# ldo_sch.net
KiCad netlist of a schematic drawn in Altium Designer
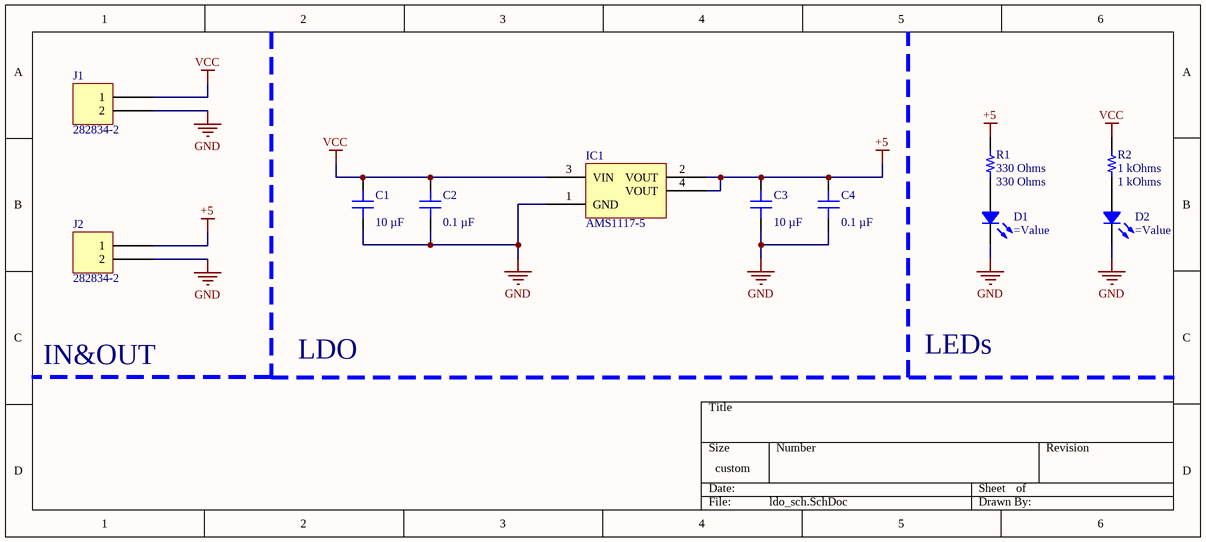
[diagram p0: ldo_sch.SchDoc]

(export (version "E")
  (design (tool "Eeschema 10.0.6"))
  (components
    (comp (ref "C1")
      (value "10 µF")
      (footprint "CAP 0603_1608")
      (description "CAP CER 10UF 10V X7R 0603")
      (fields (field (name "PART NUMBER") "GRM188Z71A106MA73D"))
      (libsource (lib "Celestial Altium Library - altium_library") (part "Capacitor"))
    )
    (comp (ref "C2")
      (value "0.1 µF")
      (footprint "CAP 0603_1608")
      (description "CAP CER 0.1UF 100V X7R 0603")
      (fields (field (name "PART NUMBER") "06031C104K4T2A"))
      (libsource (lib "Celestial Altium Library - altium_library") (part "Capacitor"))
    )
    (comp (ref "C3")
      (value "10 µF")
      (footprint "CAP 0603_1608")
      (description "CAP CER 10UF 10V X7R 0603")
      (fields (field (name "PART NUMBER") "GRM188Z71A106MA73D"))
      (libsource (lib "Celestial Altium Library - altium_library") (part "Capacitor"))
    )
    (comp (ref "C4")
      (value "0.1 µF")
      (footprint "CAP 0603_1608")
      (description "CAP CER 0.1UF 100V X7R 0603")
      (fields (field (name "PART NUMBER") "06031C104K4T2A"))
      (libsource (lib "Celestial Altium Library - altium_library") (part "Capacitor"))
    )
    (comp (ref "D1")
      (value "~")
      (footprint "LED 0603_1608 RED")
      (description "LED RED 0603")
      (fields (field (name "PART NUMBER") "APT1608SEC/J3-AMT"))
      (libsource (lib "Celestial Altium Library - altium_library") (part "LED"))
    )
    (comp (ref "D2")
      (value "~")
      (footprint "LED 0603_1608 RED")
      (description "LED RED 0603")
      (fields (field (name "PART NUMBER") "APT1608SEC/J3-AMT"))
      (libsource (lib "Celestial Altium Library - altium_library") (part "LED"))
    )
    (comp (ref "IC1")
      (value "AMS1117-5")
      (footprint "ST SOT-223")
      (description "IC REG LINEAR 5V 800MA SOT223")
      (fields (field (name "PART NUMBER") "LD1117S50TR"))
      (libsource (lib "Celestial Altium Library - altium_library") (part "ST LD1117"))
    )
    (comp (ref "J1")
      (value "282834-2")
      (footprint "TE 282834-2")
      (description "TERM BLK 2P SIDE ENT 2.54MM PCB")
      (libsource (lib "Celestial Altium Library - altium_library") (part "2 Pin"))
    )
    (comp (ref "J2")
      (value "282834-2")
      (footprint "TE 282834-2")
      (description "TERM BLK 2P SIDE ENT 2.54MM PCB")
      (libsource (lib "Celestial Altium Library - altium_library") (part "2 Pin"))
    )
    (comp (ref "R1")
      (value "330 Ohms")
      (footprint "RES 0603_1608")
      (description "RES 330 OHM 1% 1/10W 0603")
      (fields (field (name "PART NUMBER") "AC0603FR-10330RL") (field (name "ALTIUM_VALUE") "330 Ohms"))
      (libsource (lib "Celestial Altium Library - altium_library") (part "Resistor"))
    )
    (comp (ref "R2")
      (value "1 kOhms")
      (footprint "RES 0603_1608")
      (description "RES 1K OHM 0.1% 0.15W 0603")
      (fields (field (name "PART NUMBER") "3-2176366-6") (field (name "ALTIUM_VALUE") "1 kOhms"))
      (libsource (lib "Celestial Altium Library - altium_library") (part "Resistor"))
    )
  )
  (nets
    (net (code "1") (name "+5") (class "Default")
      (node (ref "C3") (pin "2") (pinfunction "2_2") (pintype "passive"))
      (node (ref "C4") (pin "2") (pinfunction "2_2") (pintype "passive"))
      (node (ref "IC1") (pin "2") (pinfunction "VOUT_2") (pintype "passive"))
      (node (ref "IC1") (pin "4") (pinfunction "VOUT_4") (pintype "passive"))
      (node (ref "J2") (pin "1") (pinfunction "1_1") (pintype "passive"))
      (node (ref "R1") (pin "2") (pinfunction "2_2") (pintype "passive"))
    )
    (net (code "2") (name "GND") (class "Default")
      (node (ref "C1") (pin "1") (pinfunction "1_1") (pintype "passive"))
      (node (ref "C2") (pin "1") (pinfunction "1_1") (pintype "passive"))
      (node (ref "C3") (pin "1") (pinfunction "1_1") (pintype "passive"))
      (node (ref "C4") (pin "1") (pinfunction "1_1") (pintype "passive"))
      (node (ref "D1") (pin "2") (pinfunction "2_2") (pintype "passive"))
      (node (ref "D2") (pin "2") (pinfunction "2_2") (pintype "passive"))
      (node (ref "IC1") (pin "1") (pinfunction "GND_1") (pintype "passive"))
      (node (ref "J1") (pin "2") (pinfunction "2_2") (pintype "passive"))
      (node (ref "J2") (pin "2") (pinfunction "2_2") (pintype "passive"))
    )
    (net (code "3") (name "Net-(D1-Pad1)") (class "Default")
      (node (ref "D1") (pin "1") (pinfunction "1_1") (pintype "passive"))
      (node (ref "R1") (pin "1") (pinfunction "1_1") (pintype "passive"))
    )
    (net (code "4") (name "Net-(D2-Pad1)") (class "Default")
      (node (ref "D2") (pin "1") (pinfunction "1_1") (pintype "passive"))
      (node (ref "R2") (pin "1") (pinfunction "1_1") (pintype "passive"))
    )
    (net (code "5") (name "VCC") (class "Default")
      (node (ref "C1") (pin "2") (pinfunction "2_2") (pintype "passive"))
      (node (ref "C2") (pin "2") (pinfunction "2_2") (pintype "passive"))
      (node (ref "IC1") (pin "3") (pinfunction "VIN_3") (pintype "passive"))
      (node (ref "J1") (pin "1") (pinfunction "1_1") (pintype "passive"))
      (node (ref "R2") (pin "2") (pinfunction "2_2") (pintype "passive"))
    )
  )
)
